# 2026Rc.net
KiCad netlist of a schematic drawn in EasyEDA Pro
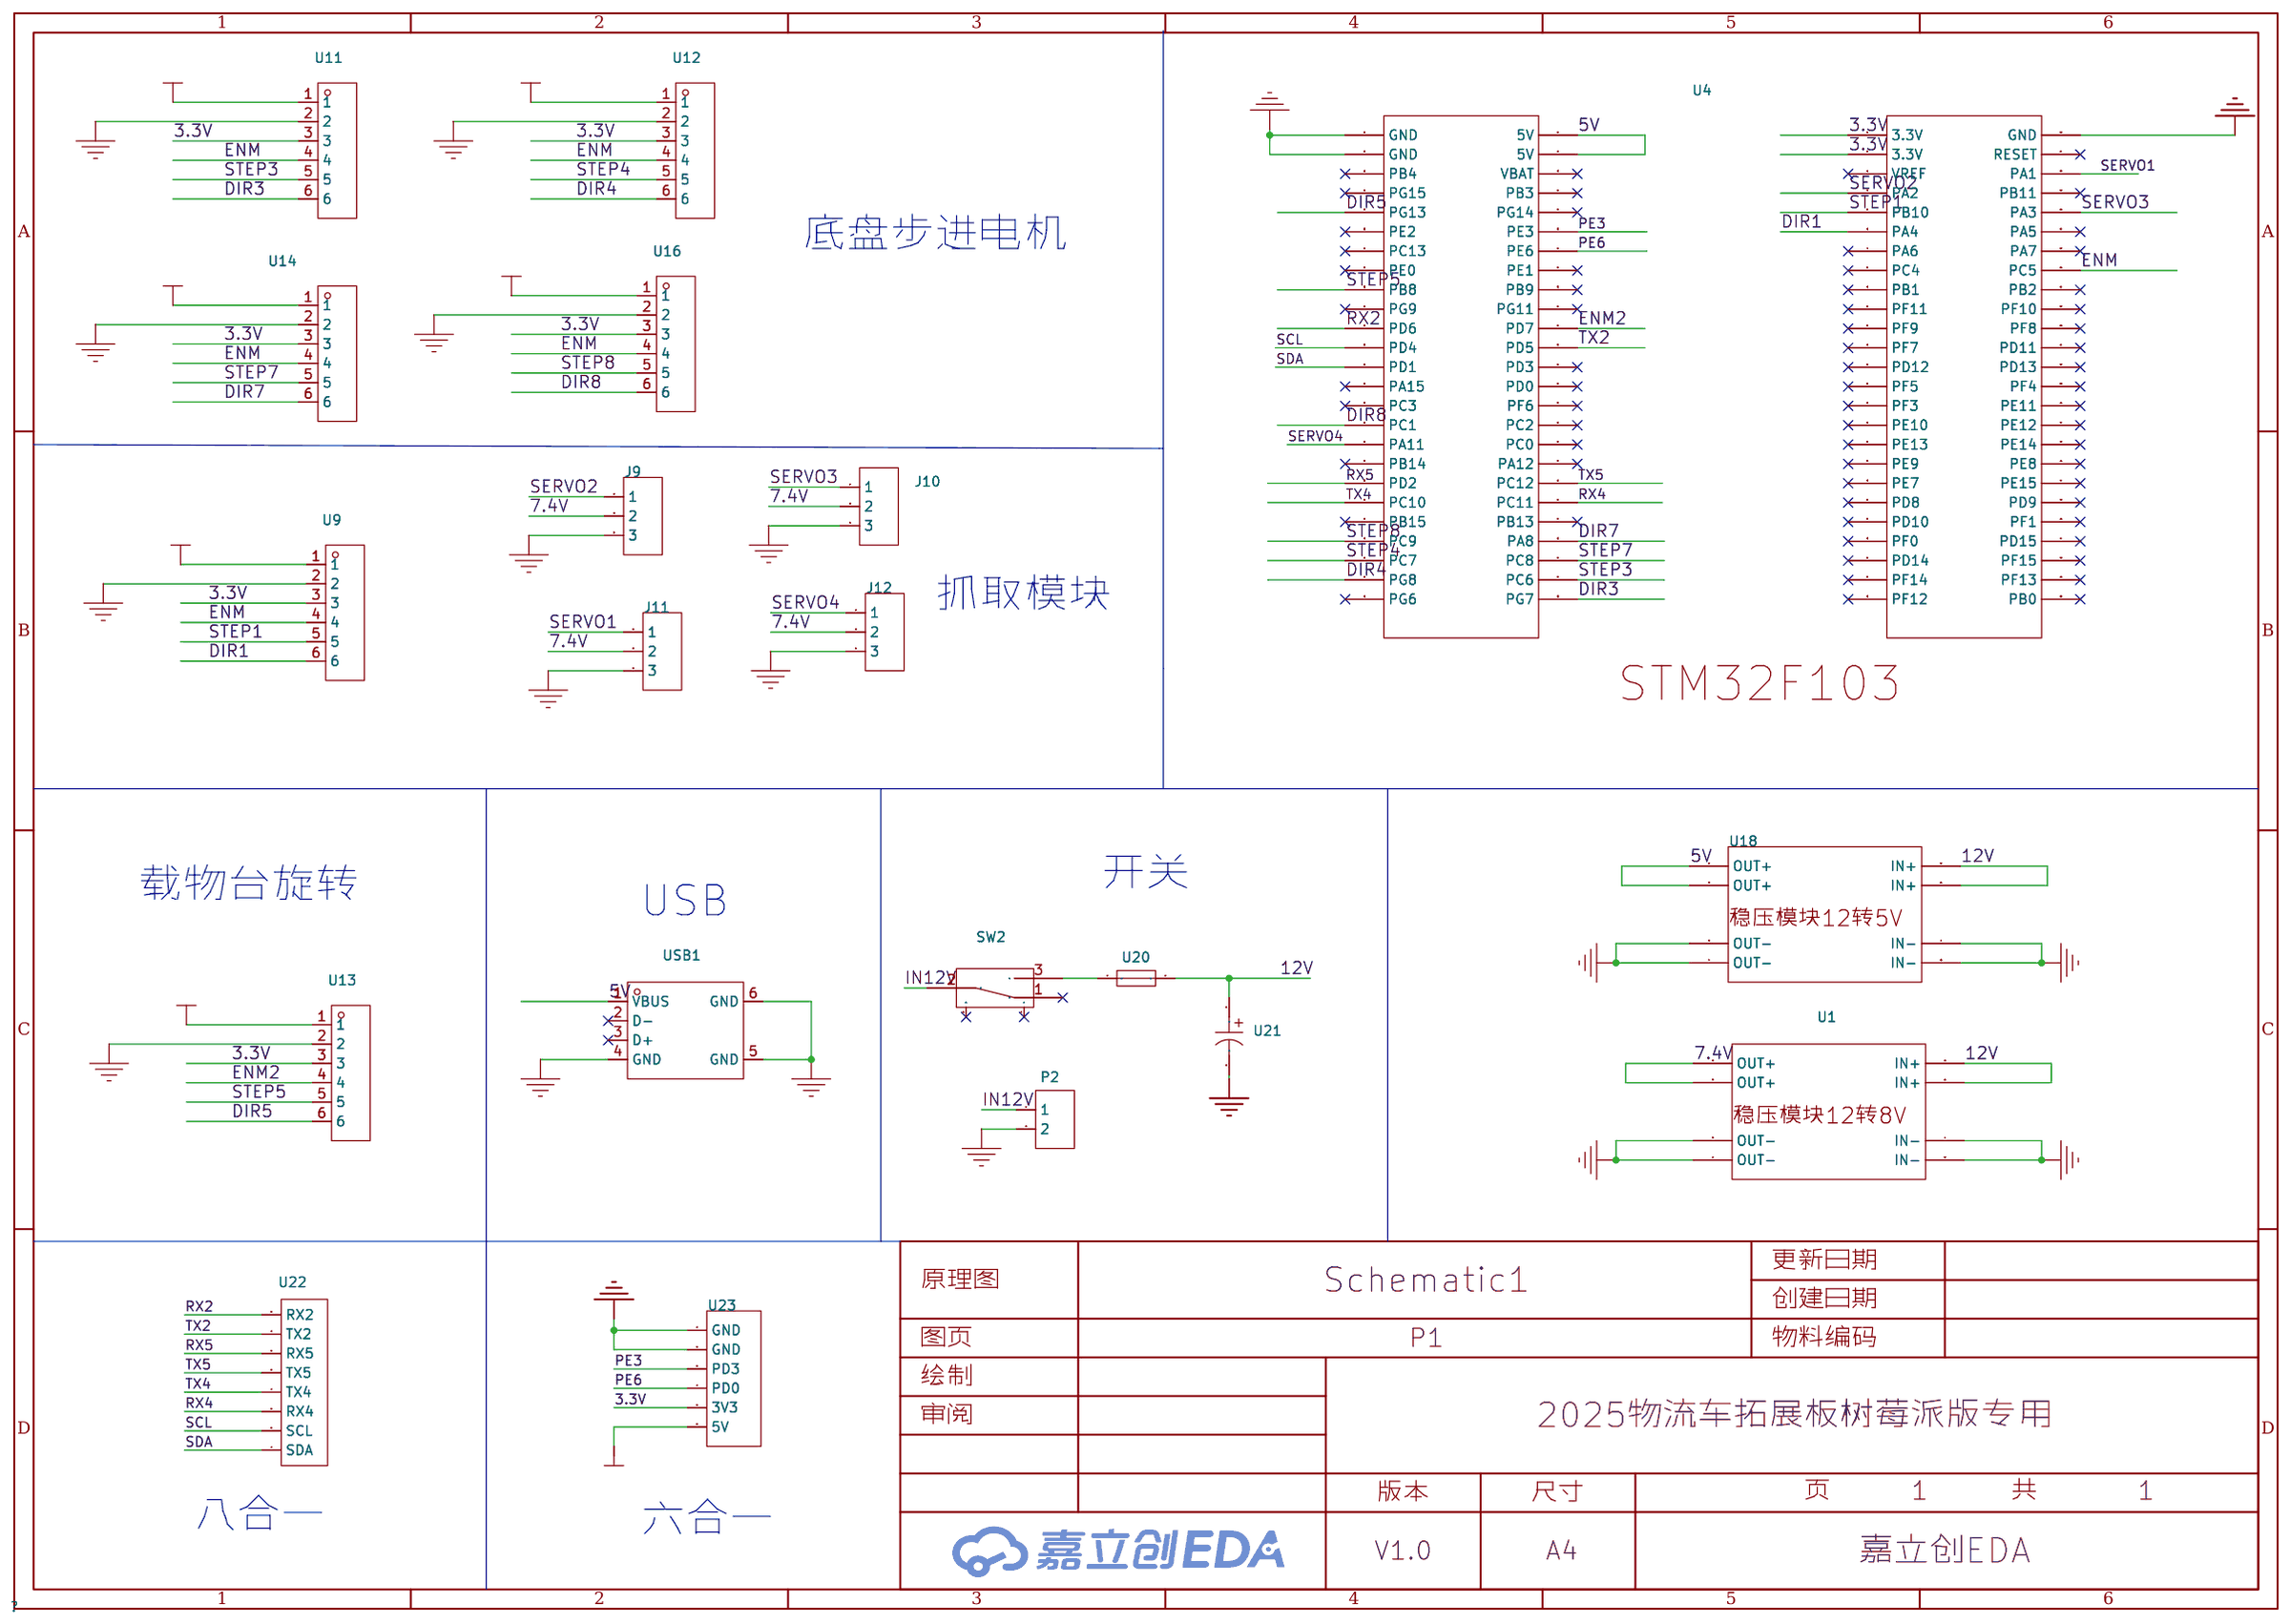
[diagram p0: schematic sheet]

(export (version "E")
  (design (tool "Eeschema 10.0.6"))
  (components
    (comp (ref "J9")
      (value "舵机2")
      (footprint "easyedapro:HDR-M-2.54_1X3")
      (libsource (lib "easyedapro") (part "舵机2"))
    )
    (comp (ref "J10")
      (value "舵机1")
      (footprint "easyedapro:HDR-M-2.54_1X3")
      (libsource (lib "easyedapro") (part "舵机1"))
    )
    (comp (ref "J11")
      (value "舵机2")
      (footprint "easyedapro:HDR-M-2.54_1X3")
      (libsource (lib "easyedapro") (part "舵机2"))
    )
    (comp (ref "J12")
      (value "舵机2")
      (footprint "easyedapro:HDR-M-2.54_1X3")
      (libsource (lib "easyedapro") (part "舵机2"))
    )
    (comp (ref "P2")
      (value "输入")
      (footprint "easyedapro:CONN-TH_2P-P5.00")
      (libsource (lib "easyedapro") (part "输入"))
    )
    (comp (ref "SW2")
      (value "SS-12F44-G5")
      (footprint "easyedapro:SW-TH_SS-12F44-G5")
      (fields (field (name "Manufacturer") "Rectangular Connectors - Contacts"))
      (libsource (lib "easyedapro") (part "SS-12F44-G5"))
    )
    (comp (ref "U1")
      (value "稳压模块12-8")
      (footprint "easyedapro:稳压模块12V到8V")
      (libsource (lib "easyedapro") (part "稳压模块12-8"))
    )
    (comp (ref "U4")
      (value "STM32_F103")
      (footprint "easyedapro:STM32F103")
      (libsource (lib "easyedapro") (part "STM32_F103"))
    )
    (comp (ref "U9")
      (value "6PIN-2.54MM")
      (footprint "easyedapro:CONN-TH_XH2.54-6P")
      (libsource (lib "easyedapro") (part "6PIN-2.54MM"))
    )
    (comp (ref "U11")
      (value "6PIN-2.54MM")
      (footprint "easyedapro:CONN-TH_XH2.54-6P")
      (libsource (lib "easyedapro") (part "6PIN-2.54MM"))
    )
    (comp (ref "U12")
      (value "6PIN-2.54MM")
      (footprint "easyedapro:CONN-TH_XH2.54-6P")
      (libsource (lib "easyedapro") (part "6PIN-2.54MM"))
    )
    (comp (ref "U13")
      (value "6PIN-2.54MM")
      (footprint "easyedapro:CONN-TH_XH2.54-6P")
      (libsource (lib "easyedapro") (part "6PIN-2.54MM"))
    )
    (comp (ref "U14")
      (value "6PIN-2.54MM")
      (footprint "easyedapro:CONN-TH_XH2.54-6P")
      (libsource (lib "easyedapro") (part "6PIN-2.54MM"))
    )
    (comp (ref "U16")
      (value "6PIN-2.54MM")
      (footprint "easyedapro:CONN-TH_XH2.54-6P")
      (libsource (lib "easyedapro") (part "6PIN-2.54MM"))
    )
    (comp (ref "U18") (value "~") (libsource (lib "easyedapro") (part "稳压模块12-5")))
    (comp (ref "U20") (value "~") (libsource (lib "easyedapro") (part "保险丝")))
    (comp (ref "U21") (value "~") (libsource (lib "easyedapro") (part "滤波电容220nf")))
    (comp (ref "U22") (value "~") (libsource (lib "easyedapro") (part "八合一")))
    (comp (ref "U23") (value "~") (libsource (lib "easyedapro") (part "六合一")))
    (comp (ref "USB1")
      (value "USB-231-ARY")
      (footprint "easyedapro:USB-A-TH_USB-231-ARY")
      (fields (field (name "Manufacturer") "XUNPU(讯普)"))
      (libsource (lib "easyedapro") (part "USB-231-ARY"))
    )
  )
  (nets
    (net (code "1") (name "/3.3V") (class "Default")
      (node (ref "U11") (pin "3") (pinfunction "3_3") (pintype "unspecified"))
      (node (ref "U12") (pin "3") (pinfunction "3_3") (pintype "unspecified"))
      (node (ref "U13") (pin "3") (pinfunction "3_3") (pintype "unspecified"))
      (node (ref "U14") (pin "3") (pinfunction "3_3") (pintype "unspecified"))
      (node (ref "U16") (pin "3") (pinfunction "3_3") (pintype "unspecified"))
      (node (ref "U23") (pin "5") (pinfunction "3V3_5") (pintype "input"))
      (node (ref "U4") (pin "1") (pinfunction "3.3V_1") (pintype "unspecified"))
      (node (ref "U4") (pin "2") (pinfunction "3.3V_2") (pintype "unspecified"))
      (node (ref "U9") (pin "3") (pinfunction "3_3") (pintype "unspecified"))
    )
    (net (code "2") (name "/7.4V") (class "Default")
      (node (ref "J10") (pin "2") (pinfunction "2_2") (pintype "unspecified"))
      (node (ref "J11") (pin "2") (pinfunction "2_2") (pintype "unspecified"))
      (node (ref "J12") (pin "2") (pinfunction "2_2") (pintype "unspecified"))
      (node (ref "J9") (pin "2") (pinfunction "2_2") (pintype "unspecified"))
      (node (ref "U1") (pin "1") (pinfunction "OUT+_1") (pintype "unspecified"))
      (node (ref "U1") (pin "2") (pinfunction "OUT+_2") (pintype "unspecified"))
    )
    (net (code "3") (name "/DIR1") (class "Default")
      (node (ref "U4") (pin "6") (pinfunction "PA4_6") (pintype "unspecified"))
      (node (ref "U9") (pin "6") (pinfunction "6_6") (pintype "unspecified"))
    )
    (net (code "4") (name "/DIR3") (class "Default")
      (node (ref "U11") (pin "6") (pinfunction "6_6") (pintype "unspecified"))
      (node (ref "U4") (pin "100") (pinfunction "PG7_100") (pintype "unspecified"))
    )
    (net (code "5") (name "/DIR4") (class "Default")
      (node (ref "U12") (pin "6") (pinfunction "6_6") (pintype "unspecified"))
      (node (ref "U4") (pin "74") (pinfunction "PG8_74") (pintype "unspecified"))
    )
    (net (code "6") (name "/DIR5") (class "Default")
      (node (ref "U13") (pin "6") (pinfunction "6_6") (pintype "unspecified"))
      (node (ref "U4") (pin "55") (pinfunction "PG13_55") (pintype "unspecified"))
    )
    (net (code "7") (name "/DIR7") (class "Default")
      (node (ref "U14") (pin "6") (pinfunction "6_6") (pintype "unspecified"))
      (node (ref "U4") (pin "97") (pinfunction "PA8_97") (pintype "unspecified"))
    )
    (net (code "8") (name "/DIR8") (class "Default")
      (node (ref "U16") (pin "6") (pinfunction "6_6") (pintype "unspecified"))
      (node (ref "U4") (pin "66") (pinfunction "PC1_66") (pintype "unspecified"))
    )
    (net (code "9") (name "/ENM") (class "Default")
      (node (ref "U11") (pin "4") (pinfunction "4_4") (pintype "unspecified"))
      (node (ref "U12") (pin "4") (pinfunction "4_4") (pintype "unspecified"))
      (node (ref "U14") (pin "4") (pinfunction "4_4") (pintype "unspecified"))
      (node (ref "U16") (pin "4") (pinfunction "4_4") (pintype "unspecified"))
      (node (ref "U4") (pin "33") (pinfunction "PC5_33") (pintype "unspecified"))
      (node (ref "U9") (pin "4") (pinfunction "4_4") (pintype "unspecified"))
    )
    (net (code "10") (name "/ENM2") (class "Default")
      (node (ref "U13") (pin "4") (pinfunction "4_4") (pintype "unspecified"))
      (node (ref "U4") (pin "86") (pinfunction "PD7_86") (pintype "unspecified"))
    )
    (net (code "11") (name "/IN12V") (class "Default")
      (node (ref "P2") (pin "1") (pinfunction "1_1") (pintype "unspecified"))
      (node (ref "SW2") (pin "2") (pinfunction "2_2") (pintype "unspecified"))
    )
    (net (code "12") (name "/PE3") (class "Default")
      (node (ref "U23") (pin "3") (pinfunction "PD3_3") (pintype "input"))
      (node (ref "U4") (pin "81") (pinfunction "PE3_81") (pintype "unspecified"))
    )
    (net (code "13") (name "/PE6") (class "Default")
      (node (ref "U23") (pin "4") (pinfunction "PD0_4") (pintype "input"))
      (node (ref "U4") (pin "82") (pinfunction "PE6_82") (pintype "unspecified"))
    )
    (net (code "14") (name "/RX2") (class "Default")
      (node (ref "U22") (pin "8") (pinfunction "RX2_8") (pintype "input"))
      (node (ref "U4") (pin "61") (pinfunction "PD6_61") (pintype "unspecified"))
    )
    (net (code "15") (name "/RX4") (class "Default")
      (node (ref "U22") (pin "5") (pinfunction "RX4_5") (pintype "input"))
      (node (ref "U4") (pin "95") (pinfunction "PC11_95") (pintype "unspecified"))
    )
    (net (code "16") (name "/RX5") (class "Default")
      (node (ref "U22") (pin "2") (pinfunction "RX5_2") (pintype "input"))
      (node (ref "U4") (pin "69") (pinfunction "PD2_69") (pintype "unspecified"))
    )
    (net (code "17") (name "/SCL") (class "Default")
      (node (ref "U22") (pin "6") (pinfunction "SCL_6") (pintype "input"))
      (node (ref "U4") (pin "62") (pinfunction "PD4_62") (pintype "unspecified"))
    )
    (net (code "18") (name "/SDA") (class "Default")
      (node (ref "U22") (pin "7") (pinfunction "SDA_7") (pintype "input"))
      (node (ref "U4") (pin "63") (pinfunction "PD1_63") (pintype "unspecified"))
    )
    (net (code "19") (name "/SERVO1") (class "Default")
      (node (ref "J11") (pin "1") (pinfunction "1_1") (pintype "unspecified"))
      (node (ref "U4") (pin "28") (pinfunction "PA1_28") (pintype "unspecified"))
    )
    (net (code "20") (name "/SERVO2") (class "Default")
      (node (ref "J9") (pin "1") (pinfunction "1_1") (pintype "unspecified"))
      (node (ref "U4") (pin "4") (pinfunction "PA2_4") (pintype "unspecified"))
    )
    (net (code "21") (name "/SERVO3") (class "Default")
      (node (ref "J10") (pin "1") (pinfunction "1_1") (pintype "unspecified"))
      (node (ref "U4") (pin "30") (pinfunction "PA3_30") (pintype "unspecified"))
    )
    (net (code "22") (name "/SERVO4") (class "Default")
      (node (ref "J12") (pin "1") (pinfunction "1_1") (pintype "unspecified"))
      (node (ref "U4") (pin "67") (pinfunction "PA11_67") (pintype "unspecified"))
    )
    (net (code "23") (name "/STEP1") (class "Default")
      (node (ref "U4") (pin "5") (pinfunction "PB10_5") (pintype "unspecified"))
      (node (ref "U9") (pin "5") (pinfunction "5_5") (pintype "unspecified"))
    )
    (net (code "24") (name "/STEP3") (class "Default")
      (node (ref "U11") (pin "5") (pinfunction "5_5") (pintype "unspecified"))
      (node (ref "U4") (pin "99") (pinfunction "PC6_99") (pintype "unspecified"))
    )
    (net (code "25") (name "/STEP4") (class "Default")
      (node (ref "U12") (pin "5") (pinfunction "5_5") (pintype "unspecified"))
      (node (ref "U4") (pin "73") (pinfunction "PC7_73") (pintype "unspecified"))
    )
    (net (code "26") (name "/STEP5") (class "Default")
      (node (ref "U13") (pin "5") (pinfunction "5_5") (pintype "unspecified"))
      (node (ref "U4") (pin "59") (pinfunction "PB8_59") (pintype "unspecified"))
    )
    (net (code "27") (name "/STEP7") (class "Default")
      (node (ref "U14") (pin "5") (pinfunction "5_5") (pintype "unspecified"))
      (node (ref "U4") (pin "98") (pinfunction "PC8_98") (pintype "unspecified"))
    )
    (net (code "28") (name "/STEP8") (class "Default")
      (node (ref "U16") (pin "5") (pinfunction "5_5") (pintype "unspecified"))
      (node (ref "U4") (pin "72") (pinfunction "PC9_72") (pintype "unspecified"))
    )
    (net (code "29") (name "/TX2") (class "Default")
      (node (ref "U22") (pin "1") (pinfunction "TX2_1") (pintype "input"))
      (node (ref "U4") (pin "87") (pinfunction "PD5_87") (pintype "unspecified"))
    )
    (net (code "30") (name "/TX4") (class "Default")
      (node (ref "U22") (pin "4") (pinfunction "TX4_4") (pintype "input"))
      (node (ref "U4") (pin "70") (pinfunction "PC10_70") (pintype "unspecified"))
    )
    (net (code "31") (name "/TX5") (class "Default")
      (node (ref "U22") (pin "3") (pinfunction "TX5_3") (pintype "input"))
      (node (ref "U4") (pin "94") (pinfunction "PC12_94") (pintype "unspecified"))
    )
    (net (code "32") (name "5V") (class "Default")
      (node (ref "U18") (pin "1") (pinfunction "OUT+_1") (pintype "unspecified"))
      (node (ref "U18") (pin "2") (pinfunction "OUT+_2") (pintype "unspecified"))
      (node (ref "U23") (pin "6") (pinfunction "5V_6") (pintype "input"))
      (node (ref "U4") (pin "76") (pinfunction "5V_76") (pintype "unspecified"))
      (node (ref "U4") (pin "77") (pinfunction "5V_77") (pintype "unspecified"))
      (node (ref "USB1") (pin "1") (pinfunction "VBUS_1") (pintype "unspecified"))
    )
    (net (code "33") (name "12V") (class "Default")
      (node (ref "U1") (pin "5") (pinfunction "IN+_5") (pintype "unspecified"))
      (node (ref "U1") (pin "6") (pinfunction "IN+_6") (pintype "unspecified"))
      (node (ref "U11") (pin "1") (pinfunction "1_1") (pintype "unspecified"))
      (node (ref "U12") (pin "1") (pinfunction "1_1") (pintype "unspecified"))
      (node (ref "U13") (pin "1") (pinfunction "1_1") (pintype "unspecified"))
      (node (ref "U14") (pin "1") (pinfunction "1_1") (pintype "unspecified"))
      (node (ref "U16") (pin "1") (pinfunction "1_1") (pintype "unspecified"))
      (node (ref "U18") (pin "5") (pinfunction "IN+_5") (pintype "unspecified"))
      (node (ref "U18") (pin "6") (pinfunction "IN+_6") (pintype "unspecified"))
      (node (ref "U20") (pin "2") (pinfunction "2_2") (pintype "unspecified"))
      (node (ref "U21") (pin "1") (pinfunction "1_1") (pintype "input"))
      (node (ref "U9") (pin "1") (pinfunction "1_1") (pintype "unspecified"))
    )
    (net (code "34") (name "GND") (class "Default")
      (node (ref "J10") (pin "3") (pinfunction "3_3") (pintype "unspecified"))
      (node (ref "J11") (pin "3") (pinfunction "3_3") (pintype "unspecified"))
      (node (ref "J12") (pin "3") (pinfunction "3_3") (pintype "unspecified"))
      (node (ref "J9") (pin "3") (pinfunction "3_3") (pintype "unspecified"))
      (node (ref "P2") (pin "2") (pinfunction "2_2") (pintype "unspecified"))
      (node (ref "U1") (pin "3") (pinfunction "OUT-_3") (pintype "unspecified"))
      (node (ref "U1") (pin "4") (pinfunction "OUT-_4") (pintype "unspecified"))
      (node (ref "U1") (pin "7") (pinfunction "IN-_7") (pintype "unspecified"))
      (node (ref "U1") (pin "8") (pinfunction "IN-_8") (pintype "unspecified"))
      (node (ref "U11") (pin "2") (pinfunction "2_2") (pintype "unspecified"))
      (node (ref "U12") (pin "2") (pinfunction "2_2") (pintype "unspecified"))
      (node (ref "U13") (pin "2") (pinfunction "2_2") (pintype "unspecified"))
      (node (ref "U14") (pin "2") (pinfunction "2_2") (pintype "unspecified"))
      (node (ref "U16") (pin "2") (pinfunction "2_2") (pintype "unspecified"))
      (node (ref "U18") (pin "3") (pinfunction "OUT-_3") (pintype "unspecified"))
      (node (ref "U18") (pin "4") (pinfunction "OUT-_4") (pintype "unspecified"))
      (node (ref "U18") (pin "7") (pinfunction "IN-_7") (pintype "unspecified"))
      (node (ref "U18") (pin "8") (pinfunction "IN-_8") (pintype "unspecified"))
      (node (ref "U21") (pin "2") (pinfunction "2_2") (pintype "input"))
      (node (ref "U23") (pin "1") (pinfunction "GND_1") (pintype "input"))
      (node (ref "U23") (pin "2") (pinfunction "GND_2") (pintype "input"))
      (node (ref "U4") (pin "26") (pinfunction "GND_26") (pintype "unspecified"))
      (node (ref "U4") (pin "51") (pinfunction "GND_51") (pintype "unspecified"))
      (node (ref "U4") (pin "52") (pinfunction "GND_52") (pintype "unspecified"))
      (node (ref "U9") (pin "2") (pinfunction "2_2") (pintype "unspecified"))
      (node (ref "USB1") (pin "4") (pinfunction "GND_4") (pintype "unspecified"))
      (node (ref "USB1") (pin "5") (pinfunction "GND_5") (pintype "unspecified"))
      (node (ref "USB1") (pin "6") (pinfunction "GND_6") (pintype "unspecified"))
    )
    (net (code "35") (name "Net-(SW2-Pad3)") (class "Default")
      (node (ref "SW2") (pin "3") (pinfunction "3_3") (pintype "unspecified"))
      (node (ref "U20") (pin "1") (pinfunction "1_1") (pintype "unspecified"))
    )
    (net (code "36") (name "unconnected-(SW2-Pad1)") (class "Default")
      (node (ref "SW2") (pin "1") (pinfunction "1_1") (pintype "unspecified+no_connect"))
    )
    (net (code "37") (name "unconnected-(SW2-Pad4)") (class "Default")
      (node (ref "SW2") (pin "4") (pinfunction "4_4") (pintype "unspecified+no_connect"))
    )
    (net (code "38") (name "unconnected-(SW2-Pad5)") (class "Default")
      (node (ref "SW2") (pin "5") (pinfunction "5_5") (pintype "unspecified+no_connect"))
    )
    (net (code "39") (name "unconnected-(U4-PA5-Pad31)") (class "Default")
      (node (ref "U4") (pin "31") (pinfunction "PA5_31") (pintype "unspecified+no_connect"))
    )
    (net (code "40") (name "unconnected-(U4-PA6-Pad7)") (class "Default")
      (node (ref "U4") (pin "7") (pinfunction "PA6_7") (pintype "unspecified+no_connect"))
    )
    (net (code "41") (name "unconnected-(U4-PA7-Pad32)") (class "Default")
      (node (ref "U4") (pin "32") (pinfunction "PA7_32") (pintype "unspecified+no_connect"))
    )
    (net (code "42") (name "unconnected-(U4-PA12-Pad93)") (class "Default")
      (node (ref "U4") (pin "93") (pinfunction "PA12_93") (pintype "unspecified+no_connect"))
    )
    (net (code "43") (name "unconnected-(U4-PA15-Pad64)") (class "Default")
      (node (ref "U4") (pin "64") (pinfunction "PA15_64") (pintype "unspecified+no_connect"))
    )
    (net (code "44") (name "unconnected-(U4-PB0-Pad50)") (class "Default")
      (node (ref "U4") (pin "50") (pinfunction "PB0_50") (pintype "unspecified+no_connect"))
    )
    (net (code "45") (name "unconnected-(U4-PB1-Pad9)") (class "Default")
      (node (ref "U4") (pin "9") (pinfunction "PB1_9") (pintype "unspecified+no_connect"))
    )
    (net (code "46") (name "unconnected-(U4-PB2-Pad34)") (class "Default")
      (node (ref "U4") (pin "34") (pinfunction "PB2_34") (pintype "unspecified+no_connect"))
    )
    (net (code "47") (name "unconnected-(U4-PB3-Pad79)") (class "Default")
      (node (ref "U4") (pin "79") (pinfunction "PB3_79") (pintype "unspecified+no_connect"))
    )
    (net (code "48") (name "unconnected-(U4-PB4-Pad53)") (class "Default")
      (node (ref "U4") (pin "53") (pinfunction "PB4_53") (pintype "unspecified+no_connect"))
    )
    (net (code "49") (name "unconnected-(U4-PB9-Pad84)") (class "Default")
      (node (ref "U4") (pin "84") (pinfunction "PB9_84") (pintype "unspecified+no_connect"))
    )
    (net (code "50") (name "unconnected-(U4-PB11-Pad29)") (class "Default")
      (node (ref "U4") (pin "29") (pinfunction "PB11_29") (pintype "unspecified+no_connect"))
    )
    (net (code "51") (name "unconnected-(U4-PB13-Pad96)") (class "Default")
      (node (ref "U4") (pin "96") (pinfunction "PB13_96") (pintype "unspecified+no_connect"))
    )
    (net (code "52") (name "unconnected-(U4-PB14-Pad68)") (class "Default")
      (node (ref "U4") (pin "68") (pinfunction "PB14_68") (pintype "unspecified+no_connect"))
    )
    (net (code "53") (name "unconnected-(U4-PB15-Pad71)") (class "Default")
      (node (ref "U4") (pin "71") (pinfunction "PB15_71") (pintype "unspecified+no_connect"))
    )
    (net (code "54") (name "unconnected-(U4-PC0-Pad92)") (class "Default")
      (node (ref "U4") (pin "92") (pinfunction "PC0_92") (pintype "unspecified+no_connect"))
    )
    (net (code "55") (name "unconnected-(U4-PC2-Pad91)") (class "Default")
      (node (ref "U4") (pin "91") (pinfunction "PC2_91") (pintype "unspecified+no_connect"))
    )
    (net (code "56") (name "unconnected-(U4-PC3-Pad65)") (class "Default")
      (node (ref "U4") (pin "65") (pinfunction "PC3_65") (pintype "unspecified+no_connect"))
    )
    (net (code "57") (name "unconnected-(U4-PC4-Pad8)") (class "Default")
      (node (ref "U4") (pin "8") (pinfunction "PC4_8") (pintype "unspecified+no_connect"))
    )
    (net (code "58") (name "unconnected-(U4-PC13-Pad57)") (class "Default")
      (node (ref "U4") (pin "57") (pinfunction "PC13_57") (pintype "unspecified+no_connect"))
    )
    (net (code "59") (name "unconnected-(U4-PD0-Pad89)") (class "Default")
      (node (ref "U4") (pin "89") (pinfunction "PD0_89") (pintype "unspecified+no_connect"))
    )
    (net (code "60") (name "unconnected-(U4-PD3-Pad88)") (class "Default")
      (node (ref "U4") (pin "88") (pinfunction "PD3_88") (pintype "unspecified+no_connect"))
    )
    (net (code "61") (name "unconnected-(U4-PD8-Pad20)") (class "Default")
      (node (ref "U4") (pin "20") (pinfunction "PD8_20") (pintype "unspecified+no_connect"))
    )
    (net (code "62") (name "unconnected-(U4-PD9-Pad45)") (class "Default")
      (node (ref "U4") (pin "45") (pinfunction "PD9_45") (pintype "unspecified+no_connect"))
    )
    (net (code "63") (name "unconnected-(U4-PD10-Pad21)") (class "Default")
      (node (ref "U4") (pin "21") (pinfunction "PD10_21") (pintype "unspecified+no_connect"))
    )
    (net (code "64") (name "unconnected-(U4-PD11-Pad37)") (class "Default")
      (node (ref "U4") (pin "37") (pinfunction "PD11_37") (pintype "unspecified+no_connect"))
    )
    (net (code "65") (name "unconnected-(U4-PD12-Pad13)") (class "Default")
      (node (ref "U4") (pin "13") (pinfunction "PD12_13") (pintype "unspecified+no_connect"))
    )
    (net (code "66") (name "unconnected-(U4-PD13-Pad38)") (class "Default")
      (node (ref "U4") (pin "38") (pinfunction "PD13_38") (pintype "unspecified+no_connect"))
    )
    (net (code "67") (name "unconnected-(U4-PD14-Pad23)") (class "Default")
      (node (ref "U4") (pin "23") (pinfunction "PD14_23") (pintype "unspecified+no_connect"))
    )
    (net (code "68") (name "unconnected-(U4-PD15-Pad47)") (class "Default")
      (node (ref "U4") (pin "47") (pinfunction "PD15_47") (pintype "unspecified+no_connect"))
    )
    (net (code "69") (name "unconnected-(U4-PE0-Pad58)") (class "Default")
      (node (ref "U4") (pin "58") (pinfunction "PE0_58") (pintype "unspecified+no_connect"))
    )
    (net (code "70") (name "unconnected-(U4-PE1-Pad83)") (class "Default")
      (node (ref "U4") (pin "83") (pinfunction "PE1_83") (pintype "unspecified+no_connect"))
    )
    (net (code "71") (name "unconnected-(U4-PE2-Pad56)") (class "Default")
      (node (ref "U4") (pin "56") (pinfunction "PE2_56") (pintype "unspecified+no_connect"))
    )
    (net (code "72") (name "unconnected-(U4-PE7-Pad19)") (class "Default")
      (node (ref "U4") (pin "19") (pinfunction "PE7_19") (pintype "unspecified+no_connect"))
    )
    (net (code "73") (name "unconnected-(U4-PE8-Pad43)") (class "Default")
      (node (ref "U4") (pin "43") (pinfunction "PE8_43") (pintype "unspecified+no_connect"))
    )
    (net (code "74") (name "unconnected-(U4-PE9-Pad18)") (class "Default")
      (node (ref "U4") (pin "18") (pinfunction "PE9_18") (pintype "unspecified+no_connect"))
    )
    (net (code "75") (name "unconnected-(U4-PE10-Pad16)") (class "Default")
      (node (ref "U4") (pin "16") (pinfunction "PE10_16") (pintype "unspecified+no_connect"))
    )
    (net (code "76") (name "unconnected-(U4-PE11-Pad40)") (class "Default")
      (node (ref "U4") (pin "40") (pinfunction "PE11_40") (pintype "unspecified+no_connect"))
    )
    (net (code "77") (name "unconnected-(U4-PE12-Pad41)") (class "Default")
      (node (ref "U4") (pin "41") (pinfunction "PE12_41") (pintype "unspecified+no_connect"))
    )
    (net (code "78") (name "unconnected-(U4-PE13-Pad17)") (class "Default")
      (node (ref "U4") (pin "17") (pinfunction "PE13_17") (pintype "unspecified+no_connect"))
    )
    (net (code "79") (name "unconnected-(U4-PE14-Pad42)") (class "Default")
      (node (ref "U4") (pin "42") (pinfunction "PE14_42") (pintype "unspecified+no_connect"))
    )
    (net (code "80") (name "unconnected-(U4-PE15-Pad44)") (class "Default")
      (node (ref "U4") (pin "44") (pinfunction "PE15_44") (pintype "unspecified+no_connect"))
    )
    (net (code "81") (name "unconnected-(U4-PF0-Pad22)") (class "Default")
      (node (ref "U4") (pin "22") (pinfunction "PF0_22") (pintype "unspecified+no_connect"))
    )
    (net (code "82") (name "unconnected-(U4-PF1-Pad46)") (class "Default")
      (node (ref "U4") (pin "46") (pinfunction "PF1_46") (pintype "unspecified+no_connect"))
    )
    (net (code "83") (name "unconnected-(U4-PF3-Pad15)") (class "Default")
      (node (ref "U4") (pin "15") (pinfunction "PF3_15") (pintype "unspecified+no_connect"))
    )
    (net (code "84") (name "unconnected-(U4-PF4-Pad39)") (class "Default")
      (node (ref "U4") (pin "39") (pinfunction "PF4_39") (pintype "unspecified+no_connect"))
    )
    (net (code "85") (name "unconnected-(U4-PF5-Pad14)") (class "Default")
      (node (ref "U4") (pin "14") (pinfunction "PF5_14") (pintype "unspecified+no_connect"))
    )
    (net (code "86") (name "unconnected-(U4-PF6-Pad90)") (class "Default")
      (node (ref "U4") (pin "90") (pinfunction "PF6_90") (pintype "unspecified+no_connect"))
    )
    (net (code "87") (name "unconnected-(U4-PF7-Pad12)") (class "Default")
      (node (ref "U4") (pin "12") (pinfunction "PF7_12") (pintype "unspecified+no_connect"))
    )
    (net (code "88") (name "unconnected-(U4-PF8-Pad36)") (class "Default")
      (node (ref "U4") (pin "36") (pinfunction "PF8_36") (pintype "unspecified+no_connect"))
    )
    (net (code "89") (name "unconnected-(U4-PF9-Pad11)") (class "Default")
      (node (ref "U4") (pin "11") (pinfunction "PF9_11") (pintype "unspecified+no_connect"))
    )
    (net (code "90") (name "unconnected-(U4-PF10-Pad35)") (class "Default")
      (node (ref "U4") (pin "35") (pinfunction "PF10_35") (pintype "unspecified+no_connect"))
    )
    (net (code "91") (name "unconnected-(U4-PF11-Pad10)") (class "Default")
      (node (ref "U4") (pin "10") (pinfunction "PF11_10") (pintype "unspecified+no_connect"))
    )
    (net (code "92") (name "unconnected-(U4-PF12-Pad25)") (class "Default")
      (node (ref "U4") (pin "25") (pinfunction "PF12_25") (pintype "unspecified+no_connect"))
    )
    (net (code "93") (name "unconnected-(U4-PF13-Pad49)") (class "Default")
      (node (ref "U4") (pin "49") (pinfunction "PF13_49") (pintype "unspecified+no_connect"))
    )
    (net (code "94") (name "unconnected-(U4-PF14-Pad24)") (class "Default")
      (node (ref "U4") (pin "24") (pinfunction "PF14_24") (pintype "unspecified+no_connect"))
    )
    (net (code "95") (name "unconnected-(U4-PF15-Pad48)") (class "Default")
      (node (ref "U4") (pin "48") (pinfunction "PF15_48") (pintype "unspecified+no_connect"))
    )
    (net (code "96") (name "unconnected-(U4-PG6-Pad75)") (class "Default")
      (node (ref "U4") (pin "75") (pinfunction "PG6_75") (pintype "unspecified+no_connect"))
    )
    (net (code "97") (name "unconnected-(U4-PG9-Pad60)") (class "Default")
      (node (ref "U4") (pin "60") (pinfunction "PG9_60") (pintype "unspecified+no_connect"))
    )
    (net (code "98") (name "unconnected-(U4-PG11-Pad85)") (class "Default")
      (node (ref "U4") (pin "85") (pinfunction "PG11_85") (pintype "unspecified+no_connect"))
    )
    (net (code "99") (name "unconnected-(U4-PG14-Pad80)") (class "Default")
      (node (ref "U4") (pin "80") (pinfunction "PG14_80") (pintype "unspecified+no_connect"))
    )
    (net (code "100") (name "unconnected-(U4-PG15-Pad54)") (class "Default")
      (node (ref "U4") (pin "54") (pinfunction "PG15_54") (pintype "unspecified+no_connect"))
    )
    (net (code "101") (name "unconnected-(U4-RESET-Pad27)") (class "Default")
      (node (ref "U4") (pin "27") (pinfunction "RESET_27") (pintype "unspecified+no_connect"))
    )
    (net (code "102") (name "unconnected-(U4-VBAT-Pad78)") (class "Default")
      (node (ref "U4") (pin "78") (pinfunction "VBAT_78") (pintype "unspecified+no_connect"))
    )
    (net (code "103") (name "unconnected-(U4-VREF-Pad3)") (class "Default")
      (node (ref "U4") (pin "3") (pinfunction "VREF_3") (pintype "unspecified+no_connect"))
    )
    (net (code "104") (name "unconnected-(USB1-D+-Pad3)") (class "Default")
      (node (ref "USB1") (pin "3") (pinfunction "D+_3") (pintype "unspecified+no_connect"))
    )
    (net (code "105") (name "unconnected-(USB1-D--Pad2)") (class "Default")
      (node (ref "USB1") (pin "2") (pinfunction "D-_2") (pintype "unspecified+no_connect"))
    )
  )
)
